# w65c265sxb_controller_rev2.net
KiCad netlist of a schematic drawn in EAGLE
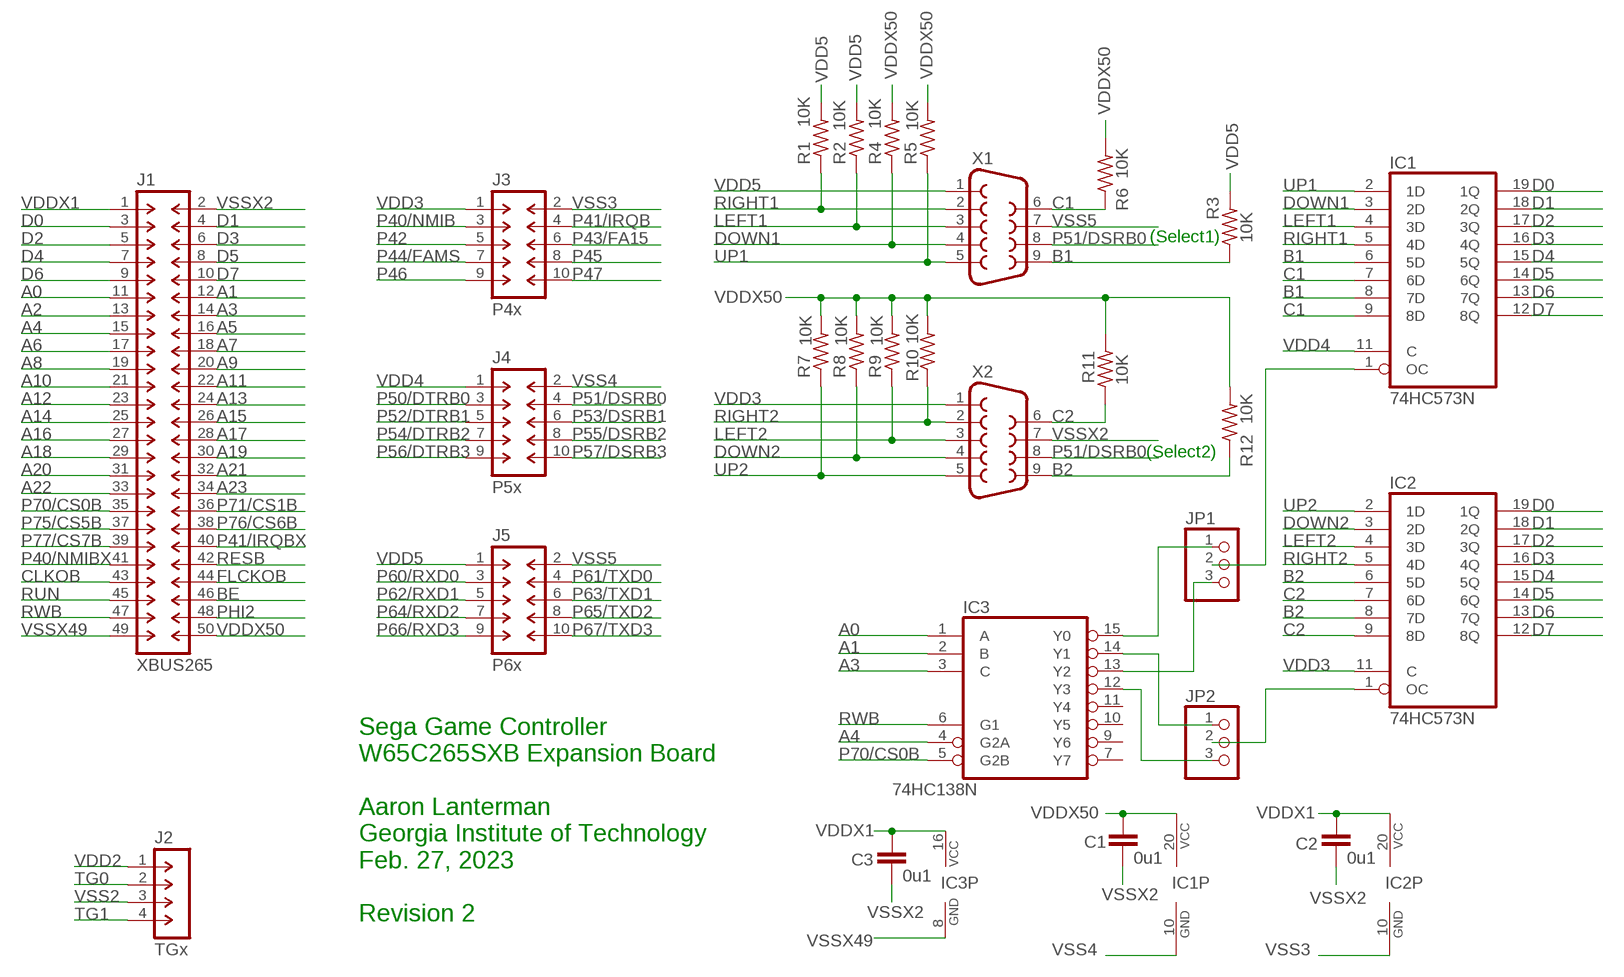
[diagram p0: schematic, sheet 1]

(export (version "E")
  (design (tool "Eeschema 10.0.6"))
  (components
    (comp (ref "C1")
      (value "0u1")
      (footprint "eagle-import:C050-025X075-AARON")
      (libsource (lib "eagle-import") (part "C-EU050-025X075-AARON"))
    )
    (comp (ref "C2")
      (value "0u1")
      (footprint "eagle-import:C050-025X075-AARON")
      (libsource (lib "eagle-import") (part "C-EU050-025X075-AARON"))
    )
    (comp (ref "C3")
      (value "0u1")
      (footprint "eagle-import:C050-025X075-AARON")
      (libsource (lib "eagle-import") (part "C-EU050-025X075-AARON"))
    )
    (comp (ref "IC1")
      (value "74HC573N")
      (footprint "eagle-import:DIL20")
      (libsource (lib "eagle-import") (part "74573NHC"))
    )
    (comp (ref "IC2")
      (value "74HC573N")
      (footprint "eagle-import:DIL20")
      (libsource (lib "eagle-import") (part "74573NHC"))
    )
    (comp (ref "IC3")
      (value "74HC138N")
      (footprint "eagle-import:DIL16")
      (libsource (lib "eagle-import") (part "74138NHC"))
    )
    (comp (ref "J1")
      (value "XBUS265")
      (footprint "eagle-import:DIL-100-2X25")
      (libsource (lib "eagle-import") (part "M-2X25-DIL-100"))
    )
    (comp (ref "J2")
      (value "TGx")
      (footprint "eagle-import:SIP-100-04-40")
      (libsource (lib "eagle-import") (part "M-1X04-SIP-100-40"))
    )
    (comp (ref "J3")
      (value "P4x")
      (footprint "eagle-import:DIL-100-2X05")
      (libsource (lib "eagle-import") (part "M-2X05-DIL-100"))
    )
    (comp (ref "J4")
      (value "P5x")
      (footprint "eagle-import:DIL-100-2X05")
      (libsource (lib "eagle-import") (part "M-2X05-DIL-100"))
    )
    (comp (ref "J5")
      (value "P6x")
      (footprint "eagle-import:DIL-100-2X05")
      (libsource (lib "eagle-import") (part "M-2X05-DIL-100"))
    )
    (comp (ref "JP1")
      (value "PINHD-1X3")
      (footprint "eagle-import:1X03")
      (libsource (lib "eagle-import") (part "PINHD-1X3"))
    )
    (comp (ref "JP2")
      (value "PINHD-1X3")
      (footprint "eagle-import:1X03")
      (libsource (lib "eagle-import") (part "PINHD-1X3"))
    )
    (comp (ref "R1")
      (value "10K")
      (footprint "eagle-import:0207_10")
      (libsource (lib "eagle-import") (part "R-US_0207/10"))
    )
    (comp (ref "R2")
      (value "10K")
      (footprint "eagle-import:0207_10")
      (libsource (lib "eagle-import") (part "R-US_0207/10"))
    )
    (comp (ref "R3")
      (value "10K")
      (footprint "eagle-import:0207_10")
      (libsource (lib "eagle-import") (part "R-US_0207/10"))
    )
    (comp (ref "R4")
      (value "10K")
      (footprint "eagle-import:0207_10")
      (libsource (lib "eagle-import") (part "R-US_0207/10"))
    )
    (comp (ref "R5")
      (value "10K")
      (footprint "eagle-import:0207_10")
      (libsource (lib "eagle-import") (part "R-US_0207/10"))
    )
    (comp (ref "R6")
      (value "10K")
      (footprint "eagle-import:0207_10")
      (libsource (lib "eagle-import") (part "R-US_0207/10"))
    )
    (comp (ref "R7")
      (value "10K")
      (footprint "eagle-import:0207_10")
      (libsource (lib "eagle-import") (part "R-US_0207/10"))
    )
    (comp (ref "R8")
      (value "10K")
      (footprint "eagle-import:0207_10")
      (libsource (lib "eagle-import") (part "R-US_0207/10"))
    )
    (comp (ref "R9")
      (value "10K")
      (footprint "eagle-import:0207_10")
      (libsource (lib "eagle-import") (part "R-US_0207/10"))
    )
    (comp (ref "R10")
      (value "10K")
      (footprint "eagle-import:0207_10")
      (libsource (lib "eagle-import") (part "R-US_0207/10"))
    )
    (comp (ref "R11")
      (value "10K")
      (footprint "eagle-import:0207_10")
      (libsource (lib "eagle-import") (part "R-US_0207/10"))
    )
    (comp (ref "R12")
      (value "10K")
      (footprint "eagle-import:0207_10")
      (libsource (lib "eagle-import") (part "R-US_0207/10"))
    )
    (comp (ref "X1")
      (value "F09HP")
      (footprint "eagle-import:F09HP")
      (libsource (lib "eagle-import") (part "F09HP"))
    )
    (comp (ref "X2")
      (value "F09HP")
      (footprint "eagle-import:F09HP")
      (libsource (lib "eagle-import") (part "F09HP"))
    )
  )
  (nets
    (net (code "1") (name "/A0") (class "Default")
      (node (ref "IC3") (pin "1") (pinfunction "A_1") (pintype "input"))
      (node (ref "J1") (pin "11") (pinfunction "11_11") (pintype "passive"))
    )
    (net (code "2") (name "/A1") (class "Default")
      (node (ref "IC3") (pin "2") (pinfunction "B_2") (pintype "input"))
      (node (ref "J1") (pin "12") (pinfunction "12_12") (pintype "passive"))
    )
    (net (code "3") (name "/A2") (class "Default")
      (node (ref "J1") (pin "13") (pinfunction "13_13") (pintype "passive"))
    )
    (net (code "4") (name "/A3") (class "Default")
      (node (ref "IC3") (pin "3") (pinfunction "C_3") (pintype "input"))
      (node (ref "J1") (pin "14") (pinfunction "14_14") (pintype "passive"))
    )
    (net (code "5") (name "/A4") (class "Default")
      (node (ref "IC3") (pin "4") (pinfunction "G2A_4") (pintype "input"))
      (node (ref "J1") (pin "15") (pinfunction "15_15") (pintype "passive"))
    )
    (net (code "6") (name "/A5") (class "Default")
      (node (ref "J1") (pin "16") (pinfunction "16_16") (pintype "passive"))
    )
    (net (code "7") (name "/A6") (class "Default")
      (node (ref "J1") (pin "17") (pinfunction "17_17") (pintype "passive"))
    )
    (net (code "8") (name "/A7") (class "Default")
      (node (ref "J1") (pin "18") (pinfunction "18_18") (pintype "passive"))
    )
    (net (code "9") (name "/A8") (class "Default")
      (node (ref "J1") (pin "19") (pinfunction "19_19") (pintype "passive"))
    )
    (net (code "10") (name "/A9") (class "Default")
      (node (ref "J1") (pin "20") (pinfunction "20_20") (pintype "passive"))
    )
    (net (code "11") (name "/A10") (class "Default")
      (node (ref "J1") (pin "21") (pinfunction "21_21") (pintype "passive"))
    )
    (net (code "12") (name "/A11") (class "Default")
      (node (ref "J1") (pin "22") (pinfunction "22_22") (pintype "passive"))
    )
    (net (code "13") (name "/A12") (class "Default")
      (node (ref "J1") (pin "23") (pinfunction "23_23") (pintype "passive"))
    )
    (net (code "14") (name "/A13") (class "Default")
      (node (ref "J1") (pin "24") (pinfunction "24_24") (pintype "passive"))
    )
    (net (code "15") (name "/A14") (class "Default")
      (node (ref "J1") (pin "25") (pinfunction "25_25") (pintype "passive"))
    )
    (net (code "16") (name "/A15") (class "Default")
      (node (ref "J1") (pin "26") (pinfunction "26_26") (pintype "passive"))
    )
    (net (code "17") (name "/A16") (class "Default")
      (node (ref "J1") (pin "27") (pinfunction "27_27") (pintype "passive"))
    )
    (net (code "18") (name "/A17") (class "Default")
      (node (ref "J1") (pin "28") (pinfunction "28_28") (pintype "passive"))
    )
    (net (code "19") (name "/A18") (class "Default")
      (node (ref "J1") (pin "29") (pinfunction "29_29") (pintype "passive"))
    )
    (net (code "20") (name "/A19") (class "Default")
      (node (ref "J1") (pin "30") (pinfunction "30_30") (pintype "passive"))
    )
    (net (code "21") (name "/A20") (class "Default")
      (node (ref "J1") (pin "31") (pinfunction "31_31") (pintype "passive"))
    )
    (net (code "22") (name "/A21") (class "Default")
      (node (ref "J1") (pin "32") (pinfunction "32_32") (pintype "passive"))
    )
    (net (code "23") (name "/A22") (class "Default")
      (node (ref "J1") (pin "33") (pinfunction "33_33") (pintype "passive"))
    )
    (net (code "24") (name "/A23") (class "Default")
      (node (ref "J1") (pin "34") (pinfunction "34_34") (pintype "passive"))
    )
    (net (code "25") (name "/B1") (class "Default")
      (node (ref "IC1") (pin "6") (pinfunction "5D_6") (pintype "input"))
      (node (ref "IC1") (pin "8") (pinfunction "7D_8") (pintype "input"))
      (node (ref "R3") (pin "1") (pinfunction "1_1") (pintype "passive"))
      (node (ref "X1") (pin "9") (pinfunction "9_9") (pintype "passive"))
    )
    (net (code "26") (name "/B2") (class "Default")
      (node (ref "IC2") (pin "6") (pinfunction "5D_6") (pintype "input"))
      (node (ref "IC2") (pin "8") (pinfunction "7D_8") (pintype "input"))
      (node (ref "R12") (pin "1") (pinfunction "1_1") (pintype "passive"))
      (node (ref "X2") (pin "9") (pinfunction "9_9") (pintype "passive"))
    )
    (net (code "27") (name "/BE") (class "Default")
      (node (ref "J1") (pin "46") (pinfunction "46_46") (pintype "passive"))
    )
    (net (code "28") (name "/C1") (class "Default")
      (node (ref "IC1") (pin "7") (pinfunction "6D_7") (pintype "input"))
      (node (ref "IC1") (pin "9") (pinfunction "8D_9") (pintype "input"))
      (node (ref "R6") (pin "1") (pinfunction "1_1") (pintype "passive"))
      (node (ref "X1") (pin "6") (pinfunction "6_6") (pintype "passive"))
    )
    (net (code "29") (name "/C2") (class "Default")
      (node (ref "IC2") (pin "7") (pinfunction "6D_7") (pintype "input"))
      (node (ref "IC2") (pin "9") (pinfunction "8D_9") (pintype "input"))
      (node (ref "R11") (pin "1") (pinfunction "1_1") (pintype "passive"))
      (node (ref "X2") (pin "6") (pinfunction "6_6") (pintype "passive"))
    )
    (net (code "30") (name "/CLKOB") (class "Default")
      (node (ref "J1") (pin "43") (pinfunction "43_43") (pintype "passive"))
    )
    (net (code "31") (name "/D0") (class "Default")
      (node (ref "IC1") (pin "19") (pinfunction "1Q_19") (pintype "tri_state"))
      (node (ref "IC2") (pin "19") (pinfunction "1Q_19") (pintype "tri_state"))
      (node (ref "J1") (pin "3") (pinfunction "3_3") (pintype "passive"))
    )
    (net (code "32") (name "/D1") (class "Default")
      (node (ref "IC1") (pin "18") (pinfunction "2Q_18") (pintype "tri_state"))
      (node (ref "IC2") (pin "18") (pinfunction "2Q_18") (pintype "tri_state"))
      (node (ref "J1") (pin "4") (pinfunction "4_4") (pintype "passive"))
    )
    (net (code "33") (name "/D2") (class "Default")
      (node (ref "IC1") (pin "17") (pinfunction "3Q_17") (pintype "tri_state"))
      (node (ref "IC2") (pin "17") (pinfunction "3Q_17") (pintype "tri_state"))
      (node (ref "J1") (pin "5") (pinfunction "5_5") (pintype "passive"))
    )
    (net (code "34") (name "/D3") (class "Default")
      (node (ref "IC1") (pin "16") (pinfunction "4Q_16") (pintype "tri_state"))
      (node (ref "IC2") (pin "16") (pinfunction "4Q_16") (pintype "tri_state"))
      (node (ref "J1") (pin "6") (pinfunction "6_6") (pintype "passive"))
    )
    (net (code "35") (name "/D4") (class "Default")
      (node (ref "IC1") (pin "15") (pinfunction "5Q_15") (pintype "tri_state"))
      (node (ref "IC2") (pin "15") (pinfunction "5Q_15") (pintype "tri_state"))
      (node (ref "J1") (pin "7") (pinfunction "7_7") (pintype "passive"))
    )
    (net (code "36") (name "/D5") (class "Default")
      (node (ref "IC1") (pin "14") (pinfunction "6Q_14") (pintype "tri_state"))
      (node (ref "IC2") (pin "14") (pinfunction "6Q_14") (pintype "tri_state"))
      (node (ref "J1") (pin "8") (pinfunction "8_8") (pintype "passive"))
    )
    (net (code "37") (name "/D6") (class "Default")
      (node (ref "IC1") (pin "13") (pinfunction "7Q_13") (pintype "tri_state"))
      (node (ref "IC2") (pin "13") (pinfunction "7Q_13") (pintype "tri_state"))
      (node (ref "J1") (pin "9") (pinfunction "9_9") (pintype "passive"))
    )
    (net (code "38") (name "/D7") (class "Default")
      (node (ref "IC1") (pin "12") (pinfunction "8Q_12") (pintype "tri_state"))
      (node (ref "IC2") (pin "12") (pinfunction "8Q_12") (pintype "tri_state"))
      (node (ref "J1") (pin "10") (pinfunction "10_10") (pintype "passive"))
    )
    (net (code "39") (name "/DOWN1") (class "Default")
      (node (ref "IC1") (pin "3") (pinfunction "2D_3") (pintype "input"))
      (node (ref "R4") (pin "1") (pinfunction "1_1") (pintype "passive"))
      (node (ref "X1") (pin "4") (pinfunction "4_4") (pintype "passive"))
    )
    (net (code "40") (name "/DOWN2") (class "Default")
      (node (ref "IC2") (pin "3") (pinfunction "2D_3") (pintype "input"))
      (node (ref "R8") (pin "1") (pinfunction "1_1") (pintype "passive"))
      (node (ref "X2") (pin "4") (pinfunction "4_4") (pintype "passive"))
    )
    (net (code "41") (name "/FLCKOB") (class "Default")
      (node (ref "J1") (pin "44") (pinfunction "44_44") (pintype "passive"))
    )
    (net (code "42") (name "/LEFT1") (class "Default")
      (node (ref "IC1") (pin "4") (pinfunction "3D_4") (pintype "input"))
      (node (ref "R2") (pin "1") (pinfunction "1_1") (pintype "passive"))
      (node (ref "X1") (pin "3") (pinfunction "3_3") (pintype "passive"))
    )
    (net (code "43") (name "/LEFT2") (class "Default")
      (node (ref "IC2") (pin "4") (pinfunction "3D_4") (pintype "input"))
      (node (ref "R9") (pin "1") (pinfunction "1_1") (pintype "passive"))
      (node (ref "X2") (pin "3") (pinfunction "3_3") (pintype "passive"))
    )
    (net (code "44") (name "/P40{slash}NMIB") (class "Default")
      (node (ref "J3") (pin "3") (pinfunction "3_3") (pintype "passive"))
    )
    (net (code "45") (name "/P40{slash}NMIBX") (class "Default")
      (node (ref "J1") (pin "41") (pinfunction "41_41") (pintype "passive"))
    )
    (net (code "46") (name "/P41{slash}IRQB") (class "Default")
      (node (ref "J3") (pin "4") (pinfunction "4_4") (pintype "passive"))
    )
    (net (code "47") (name "/P41{slash}IRQBX") (class "Default")
      (node (ref "J1") (pin "40") (pinfunction "40_40") (pintype "passive"))
    )
    (net (code "48") (name "/P42") (class "Default")
      (node (ref "J3") (pin "5") (pinfunction "5_5") (pintype "passive"))
    )
    (net (code "49") (name "/P43{slash}FA15") (class "Default")
      (node (ref "J3") (pin "6") (pinfunction "6_6") (pintype "passive"))
    )
    (net (code "50") (name "/P44{slash}FAMS") (class "Default")
      (node (ref "J3") (pin "7") (pinfunction "7_7") (pintype "passive"))
    )
    (net (code "51") (name "/P45") (class "Default")
      (node (ref "J3") (pin "8") (pinfunction "8_8") (pintype "passive"))
    )
    (net (code "52") (name "/P46") (class "Default")
      (node (ref "J3") (pin "9") (pinfunction "9_9") (pintype "passive"))
    )
    (net (code "53") (name "/P47") (class "Default")
      (node (ref "J3") (pin "10") (pinfunction "10_10") (pintype "passive"))
    )
    (net (code "54") (name "/P50{slash}DTRB0") (class "Default")
      (node (ref "J4") (pin "3") (pinfunction "3_3") (pintype "passive"))
    )
    (net (code "55") (name "/P51{slash}DSRB0") (class "Default")
      (node (ref "J4") (pin "4") (pinfunction "4_4") (pintype "passive"))
      (node (ref "X1") (pin "8") (pinfunction "8_8") (pintype "passive"))
      (node (ref "X2") (pin "8") (pinfunction "8_8") (pintype "passive"))
    )
    (net (code "56") (name "/P52{slash}DTRB1") (class "Default")
      (node (ref "J4") (pin "5") (pinfunction "5_5") (pintype "passive"))
    )
    (net (code "57") (name "/P53{slash}DSRB1") (class "Default")
      (node (ref "J4") (pin "6") (pinfunction "6_6") (pintype "passive"))
    )
    (net (code "58") (name "/P54{slash}DTRB2") (class "Default")
      (node (ref "J4") (pin "7") (pinfunction "7_7") (pintype "passive"))
    )
    (net (code "59") (name "/P55{slash}DSRB2") (class "Default")
      (node (ref "J4") (pin "8") (pinfunction "8_8") (pintype "passive"))
    )
    (net (code "60") (name "/P56{slash}DTRB3") (class "Default")
      (node (ref "J4") (pin "9") (pinfunction "9_9") (pintype "passive"))
    )
    (net (code "61") (name "/P57{slash}DSRB3") (class "Default")
      (node (ref "J4") (pin "10") (pinfunction "10_10") (pintype "passive"))
    )
    (net (code "62") (name "/P60{slash}RXD0") (class "Default")
      (node (ref "J5") (pin "3") (pinfunction "3_3") (pintype "passive"))
    )
    (net (code "63") (name "/P61{slash}TXD0") (class "Default")
      (node (ref "J5") (pin "4") (pinfunction "4_4") (pintype "passive"))
    )
    (net (code "64") (name "/P62{slash}RXD1") (class "Default")
      (node (ref "J5") (pin "5") (pinfunction "5_5") (pintype "passive"))
    )
    (net (code "65") (name "/P63{slash}TXD1") (class "Default")
      (node (ref "J5") (pin "6") (pinfunction "6_6") (pintype "passive"))
    )
    (net (code "66") (name "/P64{slash}RXD2") (class "Default")
      (node (ref "J5") (pin "7") (pinfunction "7_7") (pintype "passive"))
    )
    (net (code "67") (name "/P65{slash}TXD2") (class "Default")
      (node (ref "J5") (pin "8") (pinfunction "8_8") (pintype "passive"))
    )
    (net (code "68") (name "/P66{slash}RXD3") (class "Default")
      (node (ref "J5") (pin "9") (pinfunction "9_9") (pintype "passive"))
    )
    (net (code "69") (name "/P67{slash}TXD3") (class "Default")
      (node (ref "J5") (pin "10") (pinfunction "10_10") (pintype "passive"))
    )
    (net (code "70") (name "/P70{slash}CS0B") (class "Default")
      (node (ref "IC3") (pin "5") (pinfunction "G2B_5") (pintype "input"))
      (node (ref "J1") (pin "35") (pinfunction "35_35") (pintype "passive"))
    )
    (net (code "71") (name "/P71{slash}CS1B") (class "Default")
      (node (ref "J1") (pin "36") (pinfunction "36_36") (pintype "passive"))
    )
    (net (code "72") (name "/P75{slash}CS5B") (class "Default")
      (node (ref "J1") (pin "37") (pinfunction "37_37") (pintype "passive"))
    )
    (net (code "73") (name "/P76{slash}CS6B") (class "Default")
      (node (ref "J1") (pin "38") (pinfunction "38_38") (pintype "passive"))
    )
    (net (code "74") (name "/P77{slash}CS7B") (class "Default")
      (node (ref "J1") (pin "39") (pinfunction "39_39") (pintype "passive"))
    )
    (net (code "75") (name "/PHI2") (class "Default")
      (node (ref "J1") (pin "48") (pinfunction "48_48") (pintype "passive"))
    )
    (net (code "76") (name "/RESB") (class "Default")
      (node (ref "J1") (pin "42") (pinfunction "42_42") (pintype "passive"))
    )
    (net (code "77") (name "/RIGHT1") (class "Default")
      (node (ref "IC1") (pin "5") (pinfunction "4D_5") (pintype "input"))
      (node (ref "R1") (pin "1") (pinfunction "1_1") (pintype "passive"))
      (node (ref "X1") (pin "2") (pinfunction "2_2") (pintype "passive"))
    )
    (net (code "78") (name "/RIGHT2") (class "Default")
      (node (ref "IC2") (pin "5") (pinfunction "4D_5") (pintype "input"))
      (node (ref "R10") (pin "1") (pinfunction "1_1") (pintype "passive"))
      (node (ref "X2") (pin "2") (pinfunction "2_2") (pintype "passive"))
    )
    (net (code "79") (name "/RUN") (class "Default")
      (node (ref "J1") (pin "45") (pinfunction "45_45") (pintype "passive"))
    )
    (net (code "80") (name "/RWB") (class "Default")
      (node (ref "IC3") (pin "6") (pinfunction "G1_6") (pintype "input"))
      (node (ref "J1") (pin "47") (pinfunction "47_47") (pintype "passive"))
    )
    (net (code "81") (name "/TG0") (class "Default")
      (node (ref "J2") (pin "2") (pinfunction "2_2") (pintype "passive"))
    )
    (net (code "82") (name "/TG1") (class "Default")
      (node (ref "J2") (pin "4") (pinfunction "4_4") (pintype "passive"))
    )
    (net (code "83") (name "/UP1") (class "Default")
      (node (ref "IC1") (pin "2") (pinfunction "1D_2") (pintype "input"))
      (node (ref "R5") (pin "1") (pinfunction "1_1") (pintype "passive"))
      (node (ref "X1") (pin "5") (pinfunction "5_5") (pintype "passive"))
    )
    (net (code "84") (name "/UP2") (class "Default")
      (node (ref "IC2") (pin "2") (pinfunction "1D_2") (pintype "input"))
      (node (ref "R7") (pin "1") (pinfunction "1_1") (pintype "passive"))
      (node (ref "X2") (pin "5") (pinfunction "5_5") (pintype "passive"))
    )
    (net (code "85") (name "/VDD2") (class "Default")
      (node (ref "J2") (pin "1") (pinfunction "1_1") (pintype "passive"))
    )
    (net (code "86") (name "/VDD3") (class "Default")
      (node (ref "IC2") (pin "11") (pinfunction "C_11") (pintype "input"))
      (node (ref "J3") (pin "1") (pinfunction "1_1") (pintype "passive"))
      (node (ref "X2") (pin "1") (pinfunction "1_1") (pintype "passive"))
    )
    (net (code "87") (name "/VDD4") (class "Default")
      (node (ref "IC1") (pin "11") (pinfunction "C_11") (pintype "input"))
      (node (ref "J4") (pin "1") (pinfunction "1_1") (pintype "passive"))
    )
    (net (code "88") (name "/VDD5") (class "Default")
      (node (ref "J5") (pin "1") (pinfunction "1_1") (pintype "passive"))
      (node (ref "R1") (pin "2") (pinfunction "2_2") (pintype "passive"))
      (node (ref "R2") (pin "2") (pinfunction "2_2") (pintype "passive"))
      (node (ref "R3") (pin "2") (pinfunction "2_2") (pintype "passive"))
      (node (ref "X1") (pin "1") (pinfunction "1_1") (pintype "passive"))
    )
    (net (code "89") (name "/VDDX1") (class "Default")
      (node (ref "C2") (pin "1") (pinfunction "1_1") (pintype "passive"))
      (node (ref "C3") (pin "1") (pinfunction "1_1") (pintype "passive"))
      (node (ref "IC2") (pin "20") (pinfunction "VCC_20") (pintype "power_in"))
      (node (ref "IC3") (pin "16") (pinfunction "VCC_16") (pintype "power_in"))
      (node (ref "J1") (pin "1") (pinfunction "1_1") (pintype "passive"))
    )
    (net (code "90") (name "/VDDX50") (class "Default")
      (node (ref "C1") (pin "1") (pinfunction "1_1") (pintype "passive"))
      (node (ref "IC1") (pin "20") (pinfunction "VCC_20") (pintype "power_in"))
      (node (ref "J1") (pin "50") (pinfunction "50_50") (pintype "passive"))
      (node (ref "R10") (pin "2") (pinfunction "2_2") (pintype "passive"))
      (node (ref "R11") (pin "2") (pinfunction "2_2") (pintype "passive"))
      (node (ref "R12") (pin "2") (pinfunction "2_2") (pintype "passive"))
      (node (ref "R4") (pin "2") (pinfunction "2_2") (pintype "passive"))
      (node (ref "R5") (pin "2") (pinfunction "2_2") (pintype "passive"))
      (node (ref "R6") (pin "2") (pinfunction "2_2") (pintype "passive"))
      (node (ref "R7") (pin "2") (pinfunction "2_2") (pintype "passive"))
      (node (ref "R8") (pin "2") (pinfunction "2_2") (pintype "passive"))
      (node (ref "R9") (pin "2") (pinfunction "2_2") (pintype "passive"))
    )
    (net (code "91") (name "/VSS2") (class "Default")
      (node (ref "J2") (pin "3") (pinfunction "3_3") (pintype "passive"))
    )
    (net (code "92") (name "/VSS3") (class "Default")
      (node (ref "IC2") (pin "10") (pinfunction "GND_10") (pintype "power_in"))
      (node (ref "J3") (pin "2") (pinfunction "2_2") (pintype "passive"))
    )
    (net (code "93") (name "/VSS4") (class "Default")
      (node (ref "IC1") (pin "10") (pinfunction "GND_10") (pintype "power_in"))
      (node (ref "J4") (pin "2") (pinfunction "2_2") (pintype "passive"))
    )
    (net (code "94") (name "/VSS5") (class "Default")
      (node (ref "J5") (pin "2") (pinfunction "2_2") (pintype "passive"))
      (node (ref "X1") (pin "7") (pinfunction "7_7") (pintype "passive"))
    )
    (net (code "95") (name "/VSSX2") (class "Default")
      (node (ref "C1") (pin "2") (pinfunction "2_2") (pintype "passive"))
      (node (ref "C2") (pin "2") (pinfunction "2_2") (pintype "passive"))
      (node (ref "C3") (pin "2") (pinfunction "2_2") (pintype "passive"))
      (node (ref "J1") (pin "2") (pinfunction "2_2") (pintype "passive"))
      (node (ref "X2") (pin "7") (pinfunction "7_7") (pintype "passive"))
    )
    (net (code "96") (name "/VSSX49") (class "Default")
      (node (ref "IC3") (pin "8") (pinfunction "GND_8") (pintype "power_in"))
      (node (ref "J1") (pin "49") (pinfunction "49_49") (pintype "passive"))
    )
    (net (code "97") (name "Net-(IC1A-OC)") (class "Default")
      (node (ref "IC1") (pin "1") (pinfunction "OC_1") (pintype "input"))
      (node (ref "JP1") (pin "2") (pinfunction "2_2") (pintype "passive"))
    )
    (net (code "98") (name "Net-(IC2A-OC)") (class "Default")
      (node (ref "IC2") (pin "1") (pinfunction "OC_1") (pintype "input"))
      (node (ref "JP2") (pin "2") (pinfunction "2_2") (pintype "passive"))
    )
    (net (code "99") (name "Net-(IC3A-Y0)") (class "Default")
      (node (ref "IC3") (pin "15") (pinfunction "Y0_15") (pintype "output"))
      (node (ref "JP1") (pin "1") (pinfunction "1_1") (pintype "passive"))
    )
    (net (code "100") (name "Net-(IC3A-Y1)") (class "Default")
      (node (ref "IC3") (pin "14") (pinfunction "Y1_14") (pintype "output"))
      (node (ref "JP2") (pin "1") (pinfunction "1_1") (pintype "passive"))
    )
    (net (code "101") (name "Net-(IC3A-Y2)") (class "Default")
      (node (ref "IC3") (pin "13") (pinfunction "Y2_13") (pintype "output"))
      (node (ref "JP1") (pin "3") (pinfunction "3_3") (pintype "passive"))
    )
    (net (code "102") (name "Net-(IC3A-Y3)") (class "Default")
      (node (ref "IC3") (pin "12") (pinfunction "Y3_12") (pintype "output"))
      (node (ref "JP2") (pin "3") (pinfunction "3_3") (pintype "passive"))
    )
    (net (code "103") (name "unconnected-(IC3A-Y4-Pad11)") (class "Default")
      (node (ref "IC3") (pin "11") (pinfunction "Y4_11") (pintype "output"))
    )
    (net (code "104") (name "unconnected-(IC3A-Y5-Pad10)") (class "Default")
      (node (ref "IC3") (pin "10") (pinfunction "Y5_10") (pintype "output"))
    )
    (net (code "105") (name "unconnected-(IC3A-Y6-Pad9)") (class "Default")
      (node (ref "IC3") (pin "9") (pinfunction "Y6_9") (pintype "output"))
    )
    (net (code "106") (name "unconnected-(IC3A-Y7-Pad7)") (class "Default")
      (node (ref "IC3") (pin "7") (pinfunction "Y7_7") (pintype "output"))
    )
  )
)
